# SCH_MD001_2022-09-13.net
KiCad netlist of a schematic drawn in EasyEDA
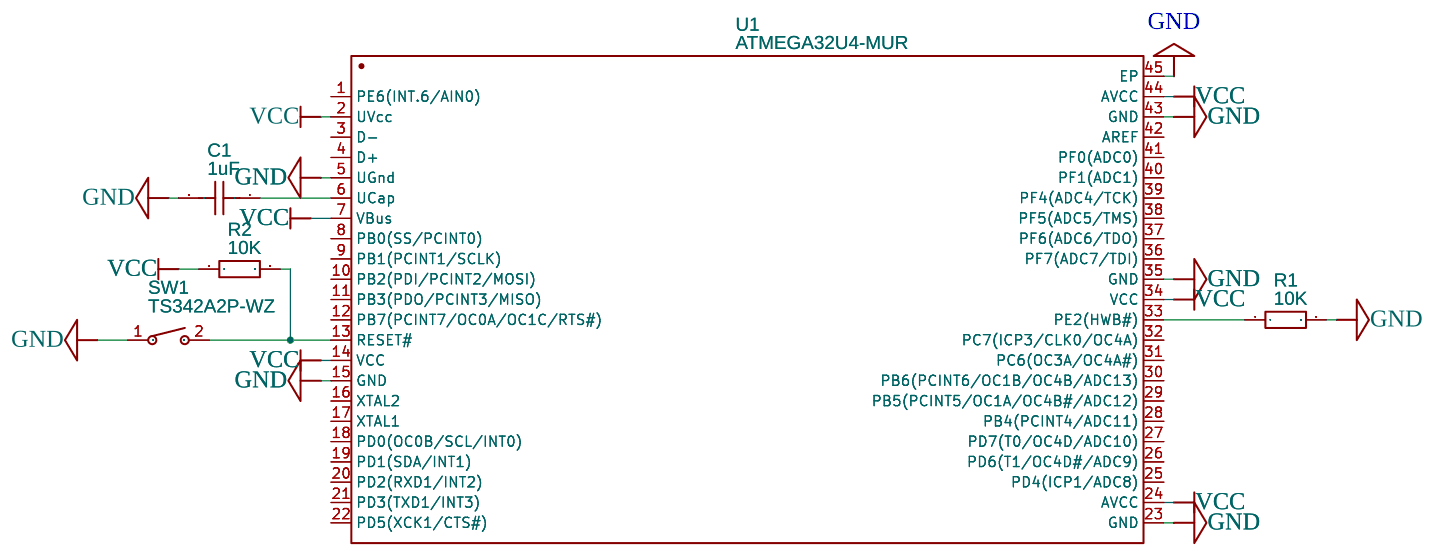
[diagram p0: schematic sheet]

(export (version "E")
  (design (tool "Eeschema 10.0.6"))
  (components
    (comp (ref "C1")
      (value "1uF")
      (fields
        (field (name "BOM_Manufacturer Part") "TCC0805X7R105K250DTS")
        (field (name "BOM_Supplier Part") "C344171")
      )
      (libsource (lib "") (part "TCC0805X7R105K250DTS"))
    )
    (comp (ref "R1")
      (value "10K")
      (fields
        (field (name "BOM_Manufacturer Part") "RT0805BRD0710KL")
        (field (name "BOM_Supplier Part") "C110775")
      )
      (libsource (lib "") (part "RT0805BRD0710KL"))
    )
    (comp (ref "R2")
      (value "10K")
      (fields
        (field (name "BOM_Manufacturer Part") "RT0805BRD0710KL")
        (field (name "BOM_Supplier Part") "C110775")
      )
      (libsource (lib "") (part "RT0805BRD0710KL"))
    )
    (comp (ref "SW1")
      (value "TS342A2P-WZ")
      (fields (field (name "BOM_Supplier Part") "C557591"))
      (libsource (lib "") (part "TS342A2P-WZ"))
    )
    (comp (ref "U1")
      (value "ATMEGA32U4-MUR")
      (fields (field (name "BOM_Supplier Part") "C45874"))
      (libsource (lib "") (part "ATMEGA32U4-MUR"))
    )
  )
  (nets
    (net (code "1") (name "GND") (class "Default")
      (node (ref "C1") (pin "2") (pinfunction "2_2") (pintype "unspecified"))
      (node (ref "R1") (pin "2") (pinfunction "2_2") (pintype "input"))
      (node (ref "SW1") (pin "1") (pinfunction "1_1") (pintype "unspecified"))
      (node (ref "U1") (pin "15") (pinfunction "GND_15") (pintype "unspecified"))
      (node (ref "U1") (pin "23") (pinfunction "GND_23") (pintype "unspecified"))
      (node (ref "U1") (pin "35") (pinfunction "GND_35") (pintype "unspecified"))
      (node (ref "U1") (pin "43") (pinfunction "GND_43") (pintype "unspecified"))
      (node (ref "U1") (pin "45") (pinfunction "EP_45") (pintype "unspecified"))
      (node (ref "U1") (pin "5") (pinfunction "UGnd_5") (pintype "unspecified"))
    )
    (net (code "2") (name "Net-(U1-PE2(HWB#))") (class "Default")
      (node (ref "R1") (pin "1") (pinfunction "1_1") (pintype "input"))
      (node (ref "U1") (pin "33") (pinfunction "PE2(HWB#)_33") (pintype "unspecified"))
    )
    (net (code "3") (name "Net-(U1-RESET#)") (class "Default")
      (node (ref "R2") (pin "2") (pinfunction "2_2") (pintype "input"))
      (node (ref "SW1") (pin "2") (pinfunction "2_2") (pintype "unspecified"))
      (node (ref "U1") (pin "13") (pinfunction "RESET#_13") (pintype "unspecified"))
    )
    (net (code "4") (name "Net-(U1-UCap)") (class "Default")
      (node (ref "C1") (pin "1") (pinfunction "1_1") (pintype "unspecified"))
      (node (ref "U1") (pin "6") (pinfunction "UCap_6") (pintype "unspecified"))
    )
    (net (code "5") (name "VCC") (class "Default")
      (node (ref "R2") (pin "1") (pinfunction "1_1") (pintype "input"))
      (node (ref "U1") (pin "14") (pinfunction "VCC_14") (pintype "unspecified"))
      (node (ref "U1") (pin "2") (pinfunction "UVcc_2") (pintype "unspecified"))
      (node (ref "U1") (pin "24") (pinfunction "AVCC_24") (pintype "unspecified"))
      (node (ref "U1") (pin "34") (pinfunction "VCC_34") (pintype "unspecified"))
      (node (ref "U1") (pin "44") (pinfunction "AVCC_44") (pintype "unspecified"))
      (node (ref "U1") (pin "7") (pinfunction "VBus_7") (pintype "unspecified"))
    )
    (net (code "6") (name "unconnected-(U1-AREF-Pad42)") (class "Default")
      (node (ref "U1") (pin "42") (pinfunction "AREF_42") (pintype "unspecified"))
    )
    (net (code "7") (name "unconnected-(U1-D+-Pad4)") (class "Default")
      (node (ref "U1") (pin "4") (pinfunction "D+_4") (pintype "unspecified"))
    )
    (net (code "8") (name "unconnected-(U1-D--Pad3)") (class "Default")
      (node (ref "U1") (pin "3") (pinfunction "D-_3") (pintype "unspecified"))
    )
    (net (code "9") (name "unconnected-(U1-PB0(SS{slash}PCINT0)-Pad8)") (class "Default")
      (node (ref "U1") (pin "8") (pinfunction "PB0(SS/PCINT0)_8") (pintype "unspecified"))
    )
    (net (code "10") (name "unconnected-(U1-PB1(PCINT1{slash}SCLK)-Pad9)") (class "Default")
      (node (ref "U1") (pin "9") (pinfunction "PB1(PCINT1/SCLK)_9") (pintype "unspecified"))
    )
    (net (code "11") (name "unconnected-(U1-PB2(PDI{slash}PCINT2{slash}MOSI)-Pad10)") (class "Default")
      (node (ref "U1") (pin "10") (pinfunction "PB2(PDI/PCINT2/MOSI)_10") (pintype "unspecified"))
    )
    (net (code "12") (name "unconnected-(U1-PB3(PDO{slash}PCINT3{slash}MISO)-Pad11)") (class "Default")
      (node (ref "U1") (pin "11") (pinfunction "PB3(PDO/PCINT3/MISO)_11") (pintype "unspecified"))
    )
    (net (code "13") (name "unconnected-(U1-PB4(PCINT4{slash}ADC11)-Pad28)") (class "Default")
      (node (ref "U1") (pin "28") (pinfunction "PB4(PCINT4/ADC11)_28") (pintype "unspecified"))
    )
    (net (code "14") (name "unconnected-(U1-PB5(PCINT5{slash}OC1A{slash}OC4B#{slash}ADC12)-Pad29)") (class "Default")
      (node (ref "U1") (pin "29") (pinfunction "PB5(PCINT5/OC1A/OC4B#/ADC12)_29") (pintype "unspecified"))
    )
    (net (code "15") (name "unconnected-(U1-PB6(PCINT6{slash}OC1B{slash}OC4B{slash}ADC13)-Pad30)") (class "Default")
      (node (ref "U1") (pin "30") (pinfunction "PB6(PCINT6/OC1B/OC4B/ADC13)_30") (pintype "unspecified"))
    )
    (net (code "16") (name "unconnected-(U1-PB7(PCINT7{slash}OC0A{slash}OC1C{slash}RTS#)-Pad12)") (class "Default")
      (node (ref "U1") (pin "12") (pinfunction "PB7(PCINT7/OC0A/OC1C/RTS#)_12") (pintype "unspecified"))
    )
    (net (code "17") (name "unconnected-(U1-PC6(OC3A{slash}OC4A#)-Pad31)") (class "Default")
      (node (ref "U1") (pin "31") (pinfunction "PC6(OC3A/OC4A#)_31") (pintype "unspecified"))
    )
    (net (code "18") (name "unconnected-(U1-PC7(ICP3{slash}CLK0{slash}OC4A)-Pad32)") (class "Default")
      (node (ref "U1") (pin "32") (pinfunction "PC7(ICP3/CLK0/OC4A)_32") (pintype "unspecified"))
    )
    (net (code "19") (name "unconnected-(U1-PD0(OC0B{slash}SCL{slash}INT0)-Pad18)") (class "Default")
      (node (ref "U1") (pin "18") (pinfunction "PD0(OC0B/SCL/INT0)_18") (pintype "unspecified"))
    )
    (net (code "20") (name "unconnected-(U1-PD1(SDA{slash}INT1)-Pad19)") (class "Default")
      (node (ref "U1") (pin "19") (pinfunction "PD1(SDA/INT1)_19") (pintype "unspecified"))
    )
    (net (code "21") (name "unconnected-(U1-PD2(RXD1{slash}INT2)-Pad20)") (class "Default")
      (node (ref "U1") (pin "20") (pinfunction "PD2(RXD1/INT2)_20") (pintype "unspecified"))
    )
    (net (code "22") (name "unconnected-(U1-PD3(TXD1{slash}INT3)-Pad21)") (class "Default")
      (node (ref "U1") (pin "21") (pinfunction "PD3(TXD1/INT3)_21") (pintype "unspecified"))
    )
    (net (code "23") (name "unconnected-(U1-PD4(ICP1{slash}ADC8)-Pad25)") (class "Default")
      (node (ref "U1") (pin "25") (pinfunction "PD4(ICP1/ADC8)_25") (pintype "unspecified"))
    )
    (net (code "24") (name "unconnected-(U1-PD5(XCK1{slash}CTS#)-Pad22)") (class "Default")
      (node (ref "U1") (pin "22") (pinfunction "PD5(XCK1/CTS#)_22") (pintype "unspecified"))
    )
    (net (code "25") (name "unconnected-(U1-PD6(T1{slash}OC4D#{slash}ADC9)-Pad26)") (class "Default")
      (node (ref "U1") (pin "26") (pinfunction "PD6(T1/OC4D#/ADC9)_26") (pintype "unspecified"))
    )
    (net (code "26") (name "unconnected-(U1-PD7(T0{slash}OC4D{slash}ADC10)-Pad27)") (class "Default")
      (node (ref "U1") (pin "27") (pinfunction "PD7(T0/OC4D/ADC10)_27") (pintype "unspecified"))
    )
    (net (code "27") (name "unconnected-(U1-PE6(INT.6{slash}AIN0)-Pad1)") (class "Default")
      (node (ref "U1") (pin "1") (pinfunction "PE6(INT.6/AIN0)_1") (pintype "unspecified"))
    )
    (net (code "28") (name "unconnected-(U1-PF0(ADC0)-Pad41)") (class "Default")
      (node (ref "U1") (pin "41") (pinfunction "PF0(ADC0)_41") (pintype "unspecified"))
    )
    (net (code "29") (name "unconnected-(U1-PF1(ADC1)-Pad40)") (class "Default")
      (node (ref "U1") (pin "40") (pinfunction "PF1(ADC1)_40") (pintype "unspecified"))
    )
    (net (code "30") (name "unconnected-(U1-PF4(ADC4{slash}TCK)-Pad39)") (class "Default")
      (node (ref "U1") (pin "39") (pinfunction "PF4(ADC4/TCK)_39") (pintype "unspecified"))
    )
    (net (code "31") (name "unconnected-(U1-PF5(ADC5{slash}TMS)-Pad38)") (class "Default")
      (node (ref "U1") (pin "38") (pinfunction "PF5(ADC5/TMS)_38") (pintype "unspecified"))
    )
    (net (code "32") (name "unconnected-(U1-PF6(ADC6{slash}TDO)-Pad37)") (class "Default")
      (node (ref "U1") (pin "37") (pinfunction "PF6(ADC6/TDO)_37") (pintype "unspecified"))
    )
    (net (code "33") (name "unconnected-(U1-PF7(ADC7{slash}TDI)-Pad36)") (class "Default")
      (node (ref "U1") (pin "36") (pinfunction "PF7(ADC7/TDI)_36") (pintype "unspecified"))
    )
    (net (code "34") (name "unconnected-(U1-XTAL1-Pad17)") (class "Default")
      (node (ref "U1") (pin "17") (pinfunction "XTAL1_17") (pintype "unspecified"))
    )
    (net (code "35") (name "unconnected-(U1-XTAL2-Pad16)") (class "Default")
      (node (ref "U1") (pin "16") (pinfunction "XTAL2_16") (pintype "unspecified"))
    )
  )
)
